# SD_Card_and_Debug_Uart.net
KiCad netlist of a schematic drawn in Altium Designer
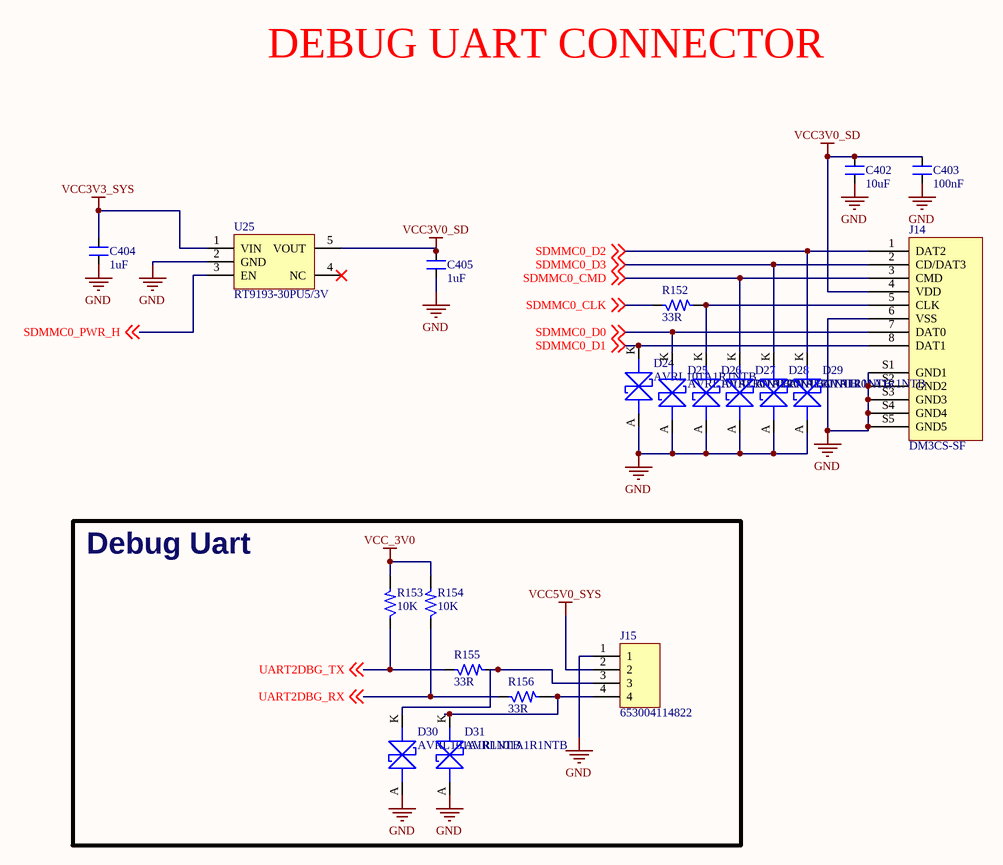
[diagram p0: SD Card and Debug Uart.SchDoc]

(export (version "E")
  (design (tool "Eeschema 10.0.6"))
  (components
    (comp (ref "C402")
      (value "10uF")
      (footprint "CAP_0603")
      (description "10µF ±10% 10V Ceramic Capacitor X5R 0603 (1608 Metric)")
      (fields
        (field (name "MANUFACTURER PART NUMBER") "GRM188R61A106KE69J")
        (field (name "MANUFACTURER") "Murata Electronics")
      )
      (libsource (lib "RK3399 _Module_Schlib") (part "CAP_10uF-10V-10%-0603"))
    )
    (comp (ref "C403")
      (value "100nF")
      (footprint "CAP_0603")
      (description "0.1µF ±10% 10V Ceramic Capacitor X7R 0603 (1608 Metric)")
      (fields
        (field (name "MANUFACTURER") "Yageo")
        (field (name "MANUFACTURER PART NUMBER") "CC0603KRX7R6BB104")
      )
      (libsource (lib "RK3399 _Module_Schlib") (part "CAP_100nF-10V-5%-0603"))
    )
    (comp (ref "C404")
      (value "1uF")
      (footprint "CAP_0603")
      (description "1µF ±10% 10V Ceramic Capacitor X5R 0603 (1608 Metric)")
      (fields
        (field (name "MANUFACTURER") "Samsung Electro-Mechanics")
        (field (name "MANUFACTURER PART NUMBER") "CL10A105KP8NNNC")
      )
      (libsource (lib "RK3399 _Module_Schlib") (part "CAP_1uF-10V-5%-0603"))
    )
    (comp (ref "C405")
      (value "1uF")
      (footprint "CAP_0603")
      (description "1µF ±10% 10V Ceramic Capacitor X5R 0603 (1608 Metric)")
      (fields
        (field (name "MANUFACTURER") "Samsung Electro-Mechanics")
        (field (name "MANUFACTURER PART NUMBER") "CL10A105KP8NNNC")
      )
      (libsource (lib "RK3399 _Module_Schlib") (part "CAP_1uF-10V-5%-0603"))
    )
    (comp (ref "D24")
      (value "AVRL101A1R1NTB")
      (footprint "DIO_0402_SMD")
      (description "39V Varistor 1 Circuit Surface Mount, MLCV 0402 (1005 Metric)")
      (fields (field (name "MANUFACTURER") "TDK Corporation"))
      (libsource (lib "RK3399 _Module_Schlib") (part "DIO-T_10V-39V-0402"))
    )
    (comp (ref "D25")
      (value "AVRL101A1R1NTB")
      (footprint "DIO_0402_SMD")
      (description "39V Varistor 1 Circuit Surface Mount, MLCV 0402 (1005 Metric)")
      (fields (field (name "MANUFACTURER") "TDK Corporation"))
      (libsource (lib "RK3399 _Module_Schlib") (part "DIO-T_10V-39V-0402"))
    )
    (comp (ref "D26")
      (value "AVRL101A1R1NTB")
      (footprint "DIO_0402_SMD")
      (description "39V Varistor 1 Circuit Surface Mount, MLCV 0402 (1005 Metric)")
      (fields (field (name "MANUFACTURER") "TDK Corporation"))
      (libsource (lib "RK3399 _Module_Schlib") (part "DIO-T_10V-39V-0402"))
    )
    (comp (ref "D27")
      (value "AVRL101A1R1NTB")
      (footprint "DIO_0402_SMD")
      (description "39V Varistor 1 Circuit Surface Mount, MLCV 0402 (1005 Metric)")
      (fields (field (name "MANUFACTURER") "TDK Corporation"))
      (libsource (lib "RK3399 _Module_Schlib") (part "DIO-T_10V-39V-0402"))
    )
    (comp (ref "D28")
      (value "AVRL101A1R1NTB")
      (footprint "DIO_0402_SMD")
      (description "39V Varistor 1 Circuit Surface Mount, MLCV 0402 (1005 Metric)")
      (fields (field (name "MANUFACTURER") "TDK Corporation"))
      (libsource (lib "RK3399 _Module_Schlib") (part "DIO-T_10V-39V-0402"))
    )
    (comp (ref "D29")
      (value "AVRL101A1R1NTB")
      (footprint "DIO_0402_SMD")
      (description "39V Varistor 1 Circuit Surface Mount, MLCV 0402 (1005 Metric)")
      (fields (field (name "MANUFACTURER") "TDK Corporation"))
      (libsource (lib "RK3399 _Module_Schlib") (part "DIO-T_10V-39V-0402"))
    )
    (comp (ref "D30")
      (value "AVRL101A1R1NTB")
      (footprint "DIO_0402_SMD")
      (description "39V Varistor 1 Circuit Surface Mount, MLCV 0402 (1005 Metric)")
      (fields (field (name "MANUFACTURER") "TDK Corporation"))
      (libsource (lib "RK3399 _Module_Schlib") (part "DIO-T_10V-39V-0402"))
    )
    (comp (ref "D31")
      (value "AVRL101A1R1NTB")
      (footprint "DIO_0402_SMD")
      (description "39V Varistor 1 Circuit Surface Mount, MLCV 0402 (1005 Metric)")
      (fields (field (name "MANUFACTURER") "TDK Corporation"))
      (libsource (lib "RK3399 _Module_Schlib") (part "DIO-T_10V-39V-0402"))
    )
    (comp (ref "J14")
      (value "DM3CS-SF")
      (footprint "CON8_43_DM3CS-SF_SMD")
      (description "Memory Card Connectors 8P R/A SMT MICRO SD HINGE PUSH-PULL")
      (fields (field (name "MANUFACTURER") "Hirose Electric Co Ltd"))
      (libsource (lib "RK3399 _Module_Schlib") (part "CON-uSD-8X1_DM3CS-SF-SMD"))
    )
    (comp (ref "J15")
      (value "653004114822")
      (footprint "CON4_50_653004114822_TH_ST")
      (description "4 Pins, 1 Row 1.25mm Pitch, straight Connector, male")
      (fields (field (name "MANUFACTURER") "JST"))
      (libsource (lib "RK3399 _Module_Schlib") (part "CON-PLG_4X1-50-ST-TH"))
    )
    (comp (ref "R152")
      (value "33R")
      (footprint "RES_0402")
      (description "33 Ohms ±1% 0.1W, 1/10W Chip Resistor 0402 (1005 Metric) Automotive AEC-Q200 Thick Film")
      (fields
        (field (name "MANUFACTURER") "Panasonic Electronic Components")
        (field (name "MANUFACTURER PART NUMBER") "ERJ-2RKF33R0X")
      )
      (libsource (lib "RK3399 _Module_Schlib") (part "RES_33R-0.1W-1%-0402"))
    )
    (comp (ref "R153")
      (value "10K")
      (footprint "RES_0603")
      (description "10 kOhms ±1% 0.1W, 1/10W Chip Resistor 0603 (1608 Metric) Thick Film")
      (fields
        (field (name "MANUFACTURER") "Yageo")
        (field (name "MANUFACTURER PART NUMBER") "RC0603FR-0710KL")
      )
      (libsource (lib "RK3399 _Module_Schlib") (part "RES_10K-0.1W-1%-0603"))
    )
    (comp (ref "R154")
      (value "10K")
      (footprint "RES_0603")
      (description "10 kOhms ±1% 0.1W, 1/10W Chip Resistor 0603 (1608 Metric) Thick Film")
      (fields
        (field (name "MANUFACTURER") "Yageo")
        (field (name "MANUFACTURER PART NUMBER") "RC0603FR-0710KL")
      )
      (libsource (lib "RK3399 _Module_Schlib") (part "RES_10K-0.1W-1%-0603"))
    )
    (comp (ref "R155")
      (value "33R")
      (footprint "RES_0402")
      (description "33 Ohms ±1% 0.1W, 1/10W Chip Resistor 0402 (1005 Metric) Automotive AEC-Q200 Thick Film")
      (fields
        (field (name "MANUFACTURER") "Panasonic Electronic Components")
        (field (name "MANUFACTURER PART NUMBER") "ERJ-2RKF33R0X")
      )
      (libsource (lib "RK3399 _Module_Schlib") (part "RES_33R-0.1W-1%-0402"))
    )
    (comp (ref "R156")
      (value "33R")
      (footprint "RES_0402")
      (description "33 Ohms ±1% 0.1W, 1/10W Chip Resistor 0402 (1005 Metric) Automotive AEC-Q200 Thick Film")
      (fields
        (field (name "MANUFACTURER") "Panasonic Electronic Components")
        (field (name "MANUFACTURER PART NUMBER") "ERJ-2RKF33R0X")
      )
      (libsource (lib "RK3399 _Module_Schlib") (part "RES_33R-0.1W-1%-0402"))
    )
    (comp (ref "U25")
      (value "RT9193-30PU5/3V")
      (footprint "SOT23-5")
      (libsource (lib "RK3399 _Module_Schlib") (part "REG_3V-5.5V-0.3A-SC-70-5"))
    )
  )
  (nets
    (net (code "1") (name "GND") (class "Default")
      (node (ref "C402") (pin "1") (pinfunction "1_1") (pintype "passive"))
      (node (ref "C403") (pin "1") (pinfunction "1_1") (pintype "passive"))
      (node (ref "C404") (pin "1") (pinfunction "1_1") (pintype "passive"))
      (node (ref "C405") (pin "1") (pinfunction "1_1") (pintype "passive"))
      (node (ref "D24") (pin "A") (pinfunction "A_A") (pintype "passive"))
      (node (ref "D25") (pin "A") (pinfunction "A_A") (pintype "passive"))
      (node (ref "D26") (pin "A") (pinfunction "A_A") (pintype "passive"))
      (node (ref "D27") (pin "A") (pinfunction "A_A") (pintype "passive"))
      (node (ref "D28") (pin "A") (pinfunction "A_A") (pintype "passive"))
      (node (ref "D29") (pin "A") (pinfunction "A_A") (pintype "passive"))
      (node (ref "D30") (pin "A") (pinfunction "A_A") (pintype "passive"))
      (node (ref "D31") (pin "A") (pinfunction "A_A") (pintype "passive"))
      (node (ref "J14") (pin "6") (pinfunction "VSS_6") (pintype "passive"))
      (node (ref "J14") (pin "S1") (pinfunction "GND1_S1") (pintype "passive"))
      (node (ref "J14") (pin "S2") (pinfunction "GND2_S2") (pintype "passive"))
      (node (ref "J14") (pin "S3") (pinfunction "GND3_S3") (pintype "passive"))
      (node (ref "J14") (pin "S4") (pinfunction "GND4_S4") (pintype "passive"))
      (node (ref "J14") (pin "S5") (pinfunction "GND5_S5") (pintype "passive"))
      (node (ref "J15") (pin "1") (pinfunction "1_1") (pintype "passive"))
      (node (ref "U25") (pin "2") (pinfunction "GND_2") (pintype "passive"))
    )
    (net (code "2") (name "Net-(D30-PadK)") (class "Default")
      (node (ref "D30") (pin "K") (pinfunction "K_K") (pintype "passive"))
      (node (ref "J15") (pin "3") (pinfunction "3_3") (pintype "passive"))
      (node (ref "R155") (pin "2") (pinfunction "2_2") (pintype "passive"))
    )
    (net (code "3") (name "Net-(D31-PadK)") (class "Default")
      (node (ref "D31") (pin "K") (pinfunction "K_K") (pintype "passive"))
      (node (ref "J15") (pin "4") (pinfunction "4_4") (pintype "passive"))
      (node (ref "R156") (pin "2") (pinfunction "2_2") (pintype "passive"))
    )
    (net (code "4") (name "Net-(J14-CLK)") (class "Default")
      (node (ref "D26") (pin "K") (pinfunction "K_K") (pintype "passive"))
      (node (ref "J14") (pin "5") (pinfunction "CLK_5") (pintype "passive"))
      (node (ref "R152") (pin "2") (pinfunction "2_2") (pintype "passive"))
    )
    (net (code "5") (name "SDMMC0_CLK") (class "Default")
      (node (ref "R152") (pin "1") (pinfunction "1_1") (pintype "passive"))
    )
    (net (code "6") (name "SDMMC0_CMD") (class "Default")
      (node (ref "D27") (pin "K") (pinfunction "K_K") (pintype "passive"))
      (node (ref "J14") (pin "3") (pinfunction "CMD_3") (pintype "passive"))
    )
    (net (code "7") (name "SDMMC0_D0") (class "Default")
      (node (ref "D25") (pin "K") (pinfunction "K_K") (pintype "passive"))
      (node (ref "J14") (pin "7") (pinfunction "DAT0_7") (pintype "passive"))
    )
    (net (code "8") (name "SDMMC0_D1") (class "Default")
      (node (ref "D24") (pin "K") (pinfunction "K_K") (pintype "passive"))
      (node (ref "J14") (pin "8") (pinfunction "DAT1_8") (pintype "passive"))
    )
    (net (code "9") (name "SDMMC0_D2") (class "Default")
      (node (ref "D29") (pin "K") (pinfunction "K_K") (pintype "passive"))
      (node (ref "J14") (pin "1") (pinfunction "DAT2_1") (pintype "passive"))
    )
    (net (code "10") (name "SDMMC0_D3") (class "Default")
      (node (ref "D28") (pin "K") (pinfunction "K_K") (pintype "passive"))
      (node (ref "J14") (pin "2") (pinfunction "CD/DAT3_2") (pintype "passive"))
    )
    (net (code "11") (name "SDMMC0_PWR_H") (class "Default")
      (node (ref "U25") (pin "3") (pinfunction "EN_3") (pintype "passive"))
    )
    (net (code "12") (name "UART2DBG_RX") (class "Default")
      (node (ref "R154") (pin "1") (pinfunction "1_1") (pintype "passive"))
      (node (ref "R156") (pin "1") (pinfunction "1_1") (pintype "passive"))
    )
    (net (code "13") (name "UART2DBG_TX") (class "Default")
      (node (ref "R153") (pin "1") (pinfunction "1_1") (pintype "passive"))
      (node (ref "R155") (pin "1") (pinfunction "1_1") (pintype "passive"))
    )
    (net (code "14") (name "VCC3V0_SD") (class "Default")
      (node (ref "C402") (pin "2") (pinfunction "2_2") (pintype "passive"))
      (node (ref "C403") (pin "2") (pinfunction "2_2") (pintype "passive"))
      (node (ref "C405") (pin "2") (pinfunction "2_2") (pintype "passive"))
      (node (ref "J14") (pin "4") (pinfunction "VDD_4") (pintype "passive"))
      (node (ref "U25") (pin "5") (pinfunction "VOUT_5") (pintype "passive"))
    )
    (net (code "15") (name "VCC3V3_SYS") (class "Default")
      (node (ref "C404") (pin "2") (pinfunction "2_2") (pintype "passive"))
      (node (ref "U25") (pin "1") (pinfunction "VIN_1") (pintype "passive"))
    )
    (net (code "16") (name "VCC5V0_SYS") (class "Default")
      (node (ref "J15") (pin "2") (pinfunction "2_2") (pintype "passive"))
    )
    (net (code "17") (name "VCC_3V0") (class "Default")
      (node (ref "R153") (pin "2") (pinfunction "2_2") (pintype "passive"))
      (node (ref "R154") (pin "2") (pinfunction "2_2") (pintype "passive"))
    )
    (net (code "18") (name "unconnected-(U25-NC-Pad4)") (class "Default")
      (node (ref "U25") (pin "4") (pinfunction "NC_4") (pintype "passive+no_connect"))
    )
  )
)
